# schematicEagle.net
KiCad netlist of a schematic drawn in EAGLE
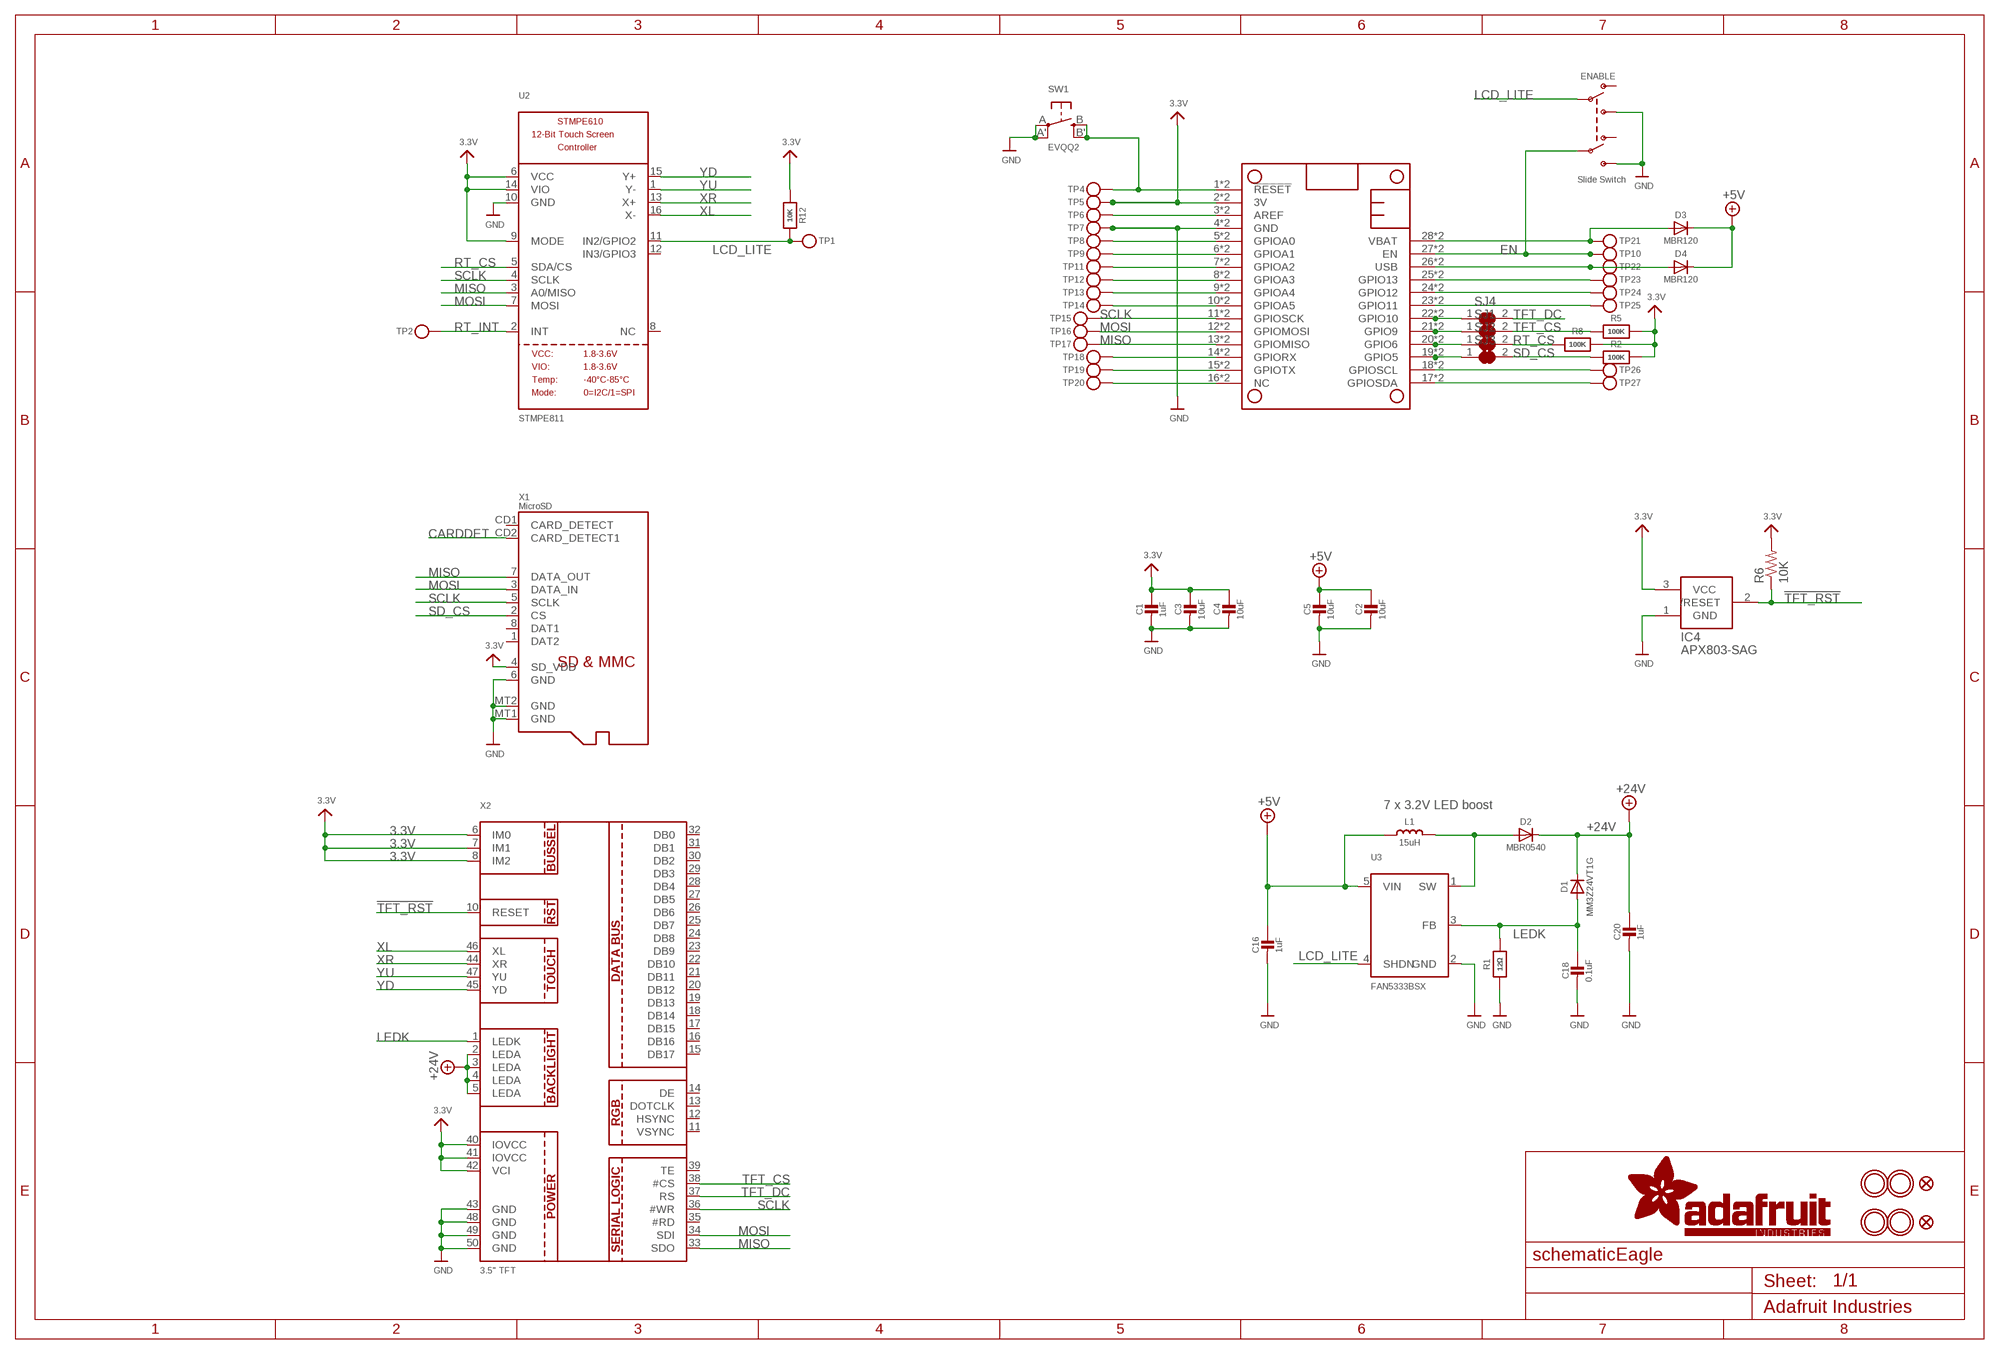
[diagram p0: schematic, sheet 1]

(export (version "E")
  (design (tool "Eeschema 10.0.6"))
  (components
    (comp (ref "C1")
      (value "1uF")
      (footprint "eagle-import:0805-NO")
      (libsource (lib "eagle-import") (part "CAP_CERAMIC0805-NOOUTLINE"))
    )
    (comp (ref "C2")
      (value "10uF")
      (footprint "eagle-import:0805-NO")
      (libsource (lib "eagle-import") (part "CAP_CERAMIC0805-NOOUTLINE"))
    )
    (comp (ref "C3")
      (value "10uF")
      (footprint "eagle-import:0805-NO")
      (libsource (lib "eagle-import") (part "CAP_CERAMIC0805-NOOUTLINE"))
    )
    (comp (ref "C4")
      (value "10uF")
      (footprint "eagle-import:0805-NO")
      (libsource (lib "eagle-import") (part "CAP_CERAMIC0805-NOOUTLINE"))
    )
    (comp (ref "C5")
      (value "10uF")
      (footprint "eagle-import:0805-NO")
      (libsource (lib "eagle-import") (part "CAP_CERAMIC0805-NOOUTLINE"))
    )
    (comp (ref "C16")
      (value "1uF")
      (footprint "eagle-import:0805-NO")
      (libsource (lib "eagle-import") (part "CAP_CERAMIC0805-NOOUTLINE"))
    )
    (comp (ref "C18")
      (value "0.1uF")
      (footprint "eagle-import:0805-NO")
      (libsource (lib "eagle-import") (part "CAP_CERAMIC0805-NOOUTLINE"))
    )
    (comp (ref "C20")
      (value "1uF")
      (footprint "eagle-import:0805-NO")
      (libsource (lib "eagle-import") (part "CAP_CERAMIC0805-NOOUTLINE"))
    )
    (comp (ref "D1")
      (value "MM3Z24VT1G")
      (footprint "eagle-import:SMADIODE")
      (libsource (lib "eagle-import") (part "DIODESMA"))
    )
    (comp (ref "D2")
      (value "MBR0540")
      (footprint "eagle-import:SOD-123")
      (libsource (lib "eagle-import") (part "DIODESOD-123"))
    )
    (comp (ref "D3")
      (value "MBR120")
      (footprint "eagle-import:SOD-123")
      (libsource (lib "eagle-import") (part "DIODESOD-123"))
    )
    (comp (ref "D4")
      (value "MBR120")
      (footprint "eagle-import:SOD-123")
      (libsource (lib "eagle-import") (part "DIODESOD-123"))
    )
    (comp (ref "ENABLE")
      (value "Slide Switch")
      (footprint "eagle-import:EG1390")
      (libsource (lib "eagle-import") (part "SWITCH_DPDTEG1390"))
    )
    (comp (ref "IC4")
      (value "APX803-SAG")
      (footprint "eagle-import:SOT23")
      (libsource (lib "eagle-import") (part "AXP083-SAG"))
    )
    (comp (ref "L1")
      (value "15uH")
      (footprint "eagle-import:INDUCTOR_5X5MM_NR5040_NOTHERMALS")
      (libsource (lib "eagle-import") (part "INDUCTORNR5040"))
    )
    (comp (ref "MS2")
      (value "FEATHERWING_SMTDUAL")
      (footprint "eagle-import:FEATHERWING_SMT2")
      (libsource (lib "eagle-import") (part "FEATHERWING_SMTDUAL"))
    )
    (comp (ref "R1")
      (value "12Ω")
      (footprint "eagle-import:0805-NO")
      (libsource (lib "eagle-import") (part "RESISTOR0805_NOOUTLINE"))
    )
    (comp (ref "R2")
      (value "100K")
      (footprint "eagle-import:0805-NO")
      (libsource (lib "eagle-import") (part "RESISTOR0805_NOOUTLINE"))
    )
    (comp (ref "R5")
      (value "100K")
      (footprint "eagle-import:0805-NO")
      (libsource (lib "eagle-import") (part "RESISTOR0805_NOOUTLINE"))
    )
    (comp (ref "R6")
      (value "10K")
      (footprint "eagle-import:R0805")
      (libsource (lib "eagle-import") (part "R-US_R0805"))
    )
    (comp (ref "R8")
      (value "100K")
      (footprint "eagle-import:0805-NO")
      (libsource (lib "eagle-import") (part "RESISTOR0805_NOOUTLINE"))
    )
    (comp (ref "R12")
      (value "10K")
      (footprint "eagle-import:0805-NO")
      (libsource (lib "eagle-import") (part "RESISTOR0805_NOOUTLINE"))
    )
    (comp (ref "SJ1")
      (value "SOLDERJUMPER_CLOSED")
      (footprint "eagle-import:SOLDERJUMPER_CLOSEDWIRE")
      (libsource (lib "eagle-import") (part "SOLDERJUMPER_CLOSED"))
    )
    (comp (ref "SJ2")
      (value "SOLDERJUMPER_CLOSED")
      (footprint "eagle-import:SOLDERJUMPER_CLOSEDWIRE")
      (libsource (lib "eagle-import") (part "SOLDERJUMPER_CLOSED"))
    )
    (comp (ref "SJ3")
      (value "SOLDERJUMPER_CLOSED")
      (footprint "eagle-import:SOLDERJUMPER_CLOSEDWIRE")
      (libsource (lib "eagle-import") (part "SOLDERJUMPER_CLOSED"))
    )
    (comp (ref "SJ4")
      (value "SOLDERJUMPER_CLOSED")
      (footprint "eagle-import:SOLDERJUMPER_CLOSEDWIRE")
      (libsource (lib "eagle-import") (part "SOLDERJUMPER_CLOSED"))
    )
    (comp (ref "SW1")
      (value "EVQQ2")
      (footprint "eagle-import:EVQ-Q2_SMALLER")
      (libsource (lib "eagle-import") (part "SWITCH_TACT_SMT_EVQQ2_SMALL"))
    )
    (comp (ref "TP1")
      (value "TESTPOINTPAD2MM")
      (footprint "eagle-import:TESTPOINT_PAD_2MM")
      (libsource (lib "eagle-import") (part "TESTPOINTPAD2MM"))
    )
    (comp (ref "TP2")
      (value "TESTPOINTPAD2MM")
      (footprint "eagle-import:TESTPOINT_PAD_2MM")
      (libsource (lib "eagle-import") (part "TESTPOINTPAD2MM"))
    )
    (comp (ref "TP4")
      (value "TESTPOINTPAD2MM")
      (footprint "eagle-import:TESTPOINT_PAD_2MM")
      (libsource (lib "eagle-import") (part "TESTPOINTPAD2MM"))
    )
    (comp (ref "TP5")
      (value "TESTPOINTPAD2MM")
      (footprint "eagle-import:TESTPOINT_PAD_2MM")
      (libsource (lib "eagle-import") (part "TESTPOINTPAD2MM"))
    )
    (comp (ref "TP6")
      (value "TESTPOINTPAD2MM")
      (footprint "eagle-import:TESTPOINT_PAD_2MM")
      (libsource (lib "eagle-import") (part "TESTPOINTPAD2MM"))
    )
    (comp (ref "TP7")
      (value "TESTPOINTPAD2MM")
      (footprint "eagle-import:TESTPOINT_PAD_2MM")
      (libsource (lib "eagle-import") (part "TESTPOINTPAD2MM"))
    )
    (comp (ref "TP8")
      (value "TESTPOINTPAD2MM")
      (footprint "eagle-import:TESTPOINT_PAD_2MM")
      (libsource (lib "eagle-import") (part "TESTPOINTPAD2MM"))
    )
    (comp (ref "TP9")
      (value "TESTPOINTPAD2MM")
      (footprint "eagle-import:TESTPOINT_PAD_2MM")
      (libsource (lib "eagle-import") (part "TESTPOINTPAD2MM"))
    )
    (comp (ref "TP10")
      (value "TESTPOINTPAD2MM")
      (footprint "eagle-import:TESTPOINT_PAD_2MM")
      (libsource (lib "eagle-import") (part "TESTPOINTPAD2MM"))
    )
    (comp (ref "TP11")
      (value "TESTPOINTPAD2MM")
      (footprint "eagle-import:TESTPOINT_PAD_2MM")
      (libsource (lib "eagle-import") (part "TESTPOINTPAD2MM"))
    )
    (comp (ref "TP12")
      (value "TESTPOINTPAD2MM")
      (footprint "eagle-import:TESTPOINT_PAD_2MM")
      (libsource (lib "eagle-import") (part "TESTPOINTPAD2MM"))
    )
    (comp (ref "TP13")
      (value "TESTPOINTPAD2MM")
      (footprint "eagle-import:TESTPOINT_PAD_2MM")
      (libsource (lib "eagle-import") (part "TESTPOINTPAD2MM"))
    )
    (comp (ref "TP14")
      (value "TESTPOINTPAD2MM")
      (footprint "eagle-import:TESTPOINT_PAD_2MM")
      (libsource (lib "eagle-import") (part "TESTPOINTPAD2MM"))
    )
    (comp (ref "TP15")
      (value "TESTPOINTPAD2MM")
      (footprint "eagle-import:TESTPOINT_PAD_2MM")
      (libsource (lib "eagle-import") (part "TESTPOINTPAD2MM"))
    )
    (comp (ref "TP16")
      (value "TESTPOINTPAD2MM")
      (footprint "eagle-import:TESTPOINT_PAD_2MM")
      (libsource (lib "eagle-import") (part "TESTPOINTPAD2MM"))
    )
    (comp (ref "TP17")
      (value "TESTPOINTPAD2MM")
      (footprint "eagle-import:TESTPOINT_PAD_2MM")
      (libsource (lib "eagle-import") (part "TESTPOINTPAD2MM"))
    )
    (comp (ref "TP18")
      (value "TESTPOINTPAD2MM")
      (footprint "eagle-import:TESTPOINT_PAD_2MM")
      (libsource (lib "eagle-import") (part "TESTPOINTPAD2MM"))
    )
    (comp (ref "TP19")
      (value "TESTPOINTPAD2MM")
      (footprint "eagle-import:TESTPOINT_PAD_2MM")
      (libsource (lib "eagle-import") (part "TESTPOINTPAD2MM"))
    )
    (comp (ref "TP20")
      (value "TESTPOINTPAD2MM")
      (footprint "eagle-import:TESTPOINT_PAD_2MM")
      (libsource (lib "eagle-import") (part "TESTPOINTPAD2MM"))
    )
    (comp (ref "TP21")
      (value "TESTPOINTPAD2MM")
      (footprint "eagle-import:TESTPOINT_PAD_2MM")
      (libsource (lib "eagle-import") (part "TESTPOINTPAD2MM"))
    )
    (comp (ref "TP22")
      (value "TESTPOINTPAD2MM")
      (footprint "eagle-import:TESTPOINT_PAD_2MM")
      (libsource (lib "eagle-import") (part "TESTPOINTPAD2MM"))
    )
    (comp (ref "TP23")
      (value "TESTPOINTPAD2MM")
      (footprint "eagle-import:TESTPOINT_PAD_2MM")
      (libsource (lib "eagle-import") (part "TESTPOINTPAD2MM"))
    )
    (comp (ref "TP24")
      (value "TESTPOINTPAD2MM")
      (footprint "eagle-import:TESTPOINT_PAD_2MM")
      (libsource (lib "eagle-import") (part "TESTPOINTPAD2MM"))
    )
    (comp (ref "TP25")
      (value "TESTPOINTPAD2MM")
      (footprint "eagle-import:TESTPOINT_PAD_2MM")
      (libsource (lib "eagle-import") (part "TESTPOINTPAD2MM"))
    )
    (comp (ref "TP26")
      (value "TESTPOINTPAD2MM")
      (footprint "eagle-import:TESTPOINT_PAD_2MM")
      (libsource (lib "eagle-import") (part "TESTPOINTPAD2MM"))
    )
    (comp (ref "TP27")
      (value "TESTPOINTPAD2MM")
      (footprint "eagle-import:TESTPOINT_PAD_2MM")
      (libsource (lib "eagle-import") (part "TESTPOINTPAD2MM"))
    )
    (comp (ref "U$7")
      (value "MOUNTINGHOLE3.0THIN")
      (footprint "eagle-import:MOUNTINGHOLE_3.0_PLATEDTHIN")
      (libsource (lib "eagle-import") (part "MOUNTINGHOLE3.0THIN"))
    )
    (comp (ref "U$9")
      (value "FIDUCIAL_1MM")
      (footprint "eagle-import:FIDUCIAL_1MM")
      (libsource (lib "eagle-import") (part "FIDUCIAL_1MM"))
    )
    (comp (ref "U$15")
      (value "MOUNTINGHOLE3.0THIN")
      (footprint "eagle-import:MOUNTINGHOLE_3.0_PLATEDTHIN")
      (libsource (lib "eagle-import") (part "MOUNTINGHOLE3.0THIN"))
    )
    (comp (ref "U$16")
      (value "MOUNTINGHOLE3.0THIN")
      (footprint "eagle-import:MOUNTINGHOLE_3.0_PLATEDTHIN")
      (libsource (lib "eagle-import") (part "MOUNTINGHOLE3.0THIN"))
    )
    (comp (ref "U$17")
      (value "MOUNTINGHOLE3.0THIN")
      (footprint "eagle-import:MOUNTINGHOLE_3.0_PLATEDTHIN")
      (libsource (lib "eagle-import") (part "MOUNTINGHOLE3.0THIN"))
    )
    (comp (ref "U$23")
      (value "FIDUCIAL_1MM")
      (footprint "eagle-import:FIDUCIAL_1MM")
      (libsource (lib "eagle-import") (part "FIDUCIAL_1MM"))
    )
    (comp (ref "U2")
      (value "STMPE811")
      (footprint "eagle-import:QFN16_3MM")
      (libsource (lib "eagle-import") (part "STMPE610"))
    )
    (comp (ref "U3")
      (value "FAN5333BSX")
      (footprint "eagle-import:SOT23-5@1")
      (libsource (lib "eagle-import") (part "FAN5331"))
    )
    (comp (ref "X1")
      (value "MicroSD")
      (footprint "eagle-import:MICROSD")
      (libsource (lib "eagle-import") (part "MICROSD"))
    )
    (comp (ref "X2")
      (value "3.5\" TFT")
      (footprint "eagle-import:TFT_3.5IN_320X480_50PIN")
      (libsource (lib "eagle-import") (part "DISP_LCD_3.5IN_320X480_50PIN"))
    )
  )
  (nets
    (net (code "1") (name "+5V") (class "Default")
      (node (ref "C16") (pin "1") (pinfunction "1_1") (pintype "passive"))
      (node (ref "C2") (pin "1") (pinfunction "1_1") (pintype "passive"))
      (node (ref "C5") (pin "1") (pinfunction "1_1") (pintype "passive"))
      (node (ref "D3") (pin "C") (pinfunction "C_C") (pintype "passive"))
      (node (ref "D4") (pin "C") (pinfunction "C_C") (pintype "passive"))
      (node (ref "L1") (pin "P$1") (pinfunction "1_P$1") (pintype "passive"))
      (node (ref "U3") (pin "5") (pinfunction "VIN_5") (pintype "bidirectional"))
    )
    (net (code "2") (name "+24V") (class "Default")
      (node (ref "C20") (pin "1") (pinfunction "1_1") (pintype "passive"))
      (node (ref "D1") (pin "C") (pinfunction "C_C") (pintype "passive"))
      (node (ref "D2") (pin "C") (pinfunction "C_C") (pintype "passive"))
      (node (ref "X2") (pin "2") (pinfunction "LEDA_2") (pintype "bidirectional"))
      (node (ref "X2") (pin "3") (pinfunction "LEDA_3") (pintype "bidirectional"))
      (node (ref "X2") (pin "4") (pinfunction "LEDA_4") (pintype "bidirectional"))
      (node (ref "X2") (pin "5") (pinfunction "LEDA_5") (pintype "bidirectional"))
    )
    (net (code "3") (name "/CARDDET") (class "Default")
      (node (ref "X1") (pin "CD2") (pinfunction "CARD_DETECT1_CD2") (pintype "passive"))
    )
    (net (code "4") (name "/EN") (class "Default")
      (node (ref "ENABLE") (pin "P2") (pinfunction "P2_P2") (pintype "passive"))
      (node (ref "MS2") (pin "27") (pinfunction "EN_27") (pintype "passive"))
      (node (ref "MS2") (pin "27'") (pinfunction "EN_27'") (pintype "passive"))
      (node (ref "TP10") (pin "P$1") (pinfunction "P$1_P$1") (pintype "bidirectional"))
    )
    (net (code "5") (name "/LCD_LITE") (class "Default")
      (node (ref "ENABLE") (pin "P1") (pinfunction "P1_P1") (pintype "passive"))
      (node (ref "R12") (pin "2") (pinfunction "2_2") (pintype "passive"))
      (node (ref "TP1") (pin "P$1") (pinfunction "P$1_P$1") (pintype "bidirectional"))
      (node (ref "U2") (pin "11") (pinfunction "IN2/GPIO2_11") (pintype "bidirectional"))
      (node (ref "U3") (pin "4") (pinfunction "SHDN_4") (pintype "bidirectional"))
    )
    (net (code "6") (name "/LEDK") (class "Default")
      (node (ref "C18") (pin "1") (pinfunction "1_1") (pintype "passive"))
      (node (ref "D1") (pin "A") (pinfunction "A_A") (pintype "passive"))
      (node (ref "R1") (pin "2") (pinfunction "2_2") (pintype "passive"))
      (node (ref "U3") (pin "3") (pinfunction "FB_3") (pintype "bidirectional"))
      (node (ref "X2") (pin "1") (pinfunction "LEDK_1") (pintype "bidirectional"))
    )
    (net (code "7") (name "/MISO") (class "Default")
      (node (ref "MS2") (pin "13") (pinfunction "GPIOMISO_13") (pintype "bidirectional"))
      (node (ref "MS2") (pin "13'") (pinfunction "GPIOMISO_13'") (pintype "bidirectional"))
      (node (ref "TP17") (pin "P$1") (pinfunction "P$1_P$1") (pintype "bidirectional"))
      (node (ref "U2") (pin "3") (pinfunction "A0/MISO_3") (pintype "bidirectional"))
      (node (ref "X1") (pin "7") (pinfunction "DATA_OUT_7") (pintype "output"))
      (node (ref "X2") (pin "33") (pinfunction "SDO_33") (pintype "bidirectional"))
    )
    (net (code "8") (name "/MOSI") (class "Default")
      (node (ref "MS2") (pin "12") (pinfunction "GPIOMOSI_12") (pintype "bidirectional"))
      (node (ref "MS2") (pin "12'") (pinfunction "GPIOMOSI_12'") (pintype "bidirectional"))
      (node (ref "TP16") (pin "P$1") (pinfunction "P$1_P$1") (pintype "bidirectional"))
      (node (ref "U2") (pin "7") (pinfunction "MOSI_7") (pintype "input"))
      (node (ref "X1") (pin "3") (pinfunction "DATA_IN_3") (pintype "input"))
      (node (ref "X2") (pin "34") (pinfunction "SDI_34") (pintype "bidirectional"))
    )
    (net (code "9") (name "/RT_CS") (class "Default")
      (node (ref "R8") (pin "1") (pinfunction "1_1") (pintype "passive"))
      (node (ref "SJ2") (pin "2") (pinfunction "2_2") (pintype "passive"))
      (node (ref "U2") (pin "5") (pinfunction "SDA/CS_5") (pintype "bidirectional"))
    )
    (net (code "10") (name "/RT_INT") (class "Default")
      (node (ref "TP2") (pin "P$1") (pinfunction "P$1_P$1") (pintype "bidirectional"))
      (node (ref "U2") (pin "2") (pinfunction "INT_2") (pintype "output"))
    )
    (net (code "11") (name "/SCLK") (class "Default")
      (node (ref "MS2") (pin "11") (pinfunction "GPIOSCK_11") (pintype "bidirectional"))
      (node (ref "MS2") (pin "11'") (pinfunction "GPIOSCK_11'") (pintype "bidirectional"))
      (node (ref "TP15") (pin "P$1") (pinfunction "P$1_P$1") (pintype "bidirectional"))
      (node (ref "U2") (pin "4") (pinfunction "SCLK_4") (pintype "bidirectional"))
      (node (ref "X1") (pin "5") (pinfunction "SCLK_5") (pintype "input"))
      (node (ref "X2") (pin "36") (pinfunction "#WR_36") (pintype "bidirectional"))
    )
    (net (code "12") (name "/SD_CS") (class "Default")
      (node (ref "R2") (pin "1") (pinfunction "1_1") (pintype "passive"))
      (node (ref "SJ3") (pin "2") (pinfunction "2_2") (pintype "passive"))
      (node (ref "X1") (pin "2") (pinfunction "CS_2") (pintype "input"))
    )
    (net (code "13") (name "/TFT_CS") (class "Default")
      (node (ref "R5") (pin "1") (pinfunction "1_1") (pintype "passive"))
      (node (ref "SJ1") (pin "2") (pinfunction "2_2") (pintype "passive"))
      (node (ref "X2") (pin "38") (pinfunction "#CS_38") (pintype "bidirectional"))
    )
    (net (code "14") (name "/TFT_DC") (class "Default")
      (node (ref "SJ4") (pin "2") (pinfunction "2_2") (pintype "passive"))
      (node (ref "X2") (pin "37") (pinfunction "RS_37") (pintype "bidirectional"))
    )
    (net (code "15") (name "/XL") (class "Default")
      (node (ref "U2") (pin "16") (pinfunction "X-_16") (pintype "input"))
      (node (ref "X2") (pin "46") (pinfunction "XL_46") (pintype "bidirectional"))
    )
    (net (code "16") (name "/XR") (class "Default")
      (node (ref "U2") (pin "13") (pinfunction "X+_13") (pintype "input"))
      (node (ref "X2") (pin "44") (pinfunction "XR_44") (pintype "bidirectional"))
    )
    (net (code "17") (name "/YD") (class "Default")
      (node (ref "U2") (pin "15") (pinfunction "Y+_15") (pintype "input"))
      (node (ref "X2") (pin "45") (pinfunction "YD_45") (pintype "bidirectional"))
    )
    (net (code "18") (name "/YU") (class "Default")
      (node (ref "U2") (pin "1") (pinfunction "Y-_1") (pintype "input"))
      (node (ref "X2") (pin "47") (pinfunction "YU_47") (pintype "bidirectional"))
    )
    (net (code "19") (name "/~{TFT_RST}") (class "Default")
      (node (ref "IC4") (pin "2") (pinfunction "/RESET_2") (pintype "output"))
      (node (ref "R6") (pin "1") (pinfunction "1_1") (pintype "passive"))
      (node (ref "X2") (pin "10") (pinfunction "RESET_10") (pintype "bidirectional"))
    )
    (net (code "20") (name "3.3V") (class "Default")
      (node (ref "C1") (pin "1") (pinfunction "1_1") (pintype "passive"))
      (node (ref "C3") (pin "1") (pinfunction "1_1") (pintype "passive"))
      (node (ref "C4") (pin "1") (pinfunction "1_1") (pintype "passive"))
      (node (ref "IC4") (pin "3") (pinfunction "VCC_3") (pintype "power_in"))
      (node (ref "MS2") (pin "2") (pinfunction "3V_2") (pintype "power_in"))
      (node (ref "MS2") (pin "2'") (pinfunction "3V_2'") (pintype "power_in"))
      (node (ref "R12") (pin "1") (pinfunction "1_1") (pintype "passive"))
      (node (ref "R2") (pin "2") (pinfunction "2_2") (pintype "passive"))
      (node (ref "R5") (pin "2") (pinfunction "2_2") (pintype "passive"))
      (node (ref "R6") (pin "2") (pinfunction "2_2") (pintype "passive"))
      (node (ref "R8") (pin "2") (pinfunction "2_2") (pintype "passive"))
      (node (ref "TP5") (pin "P$1") (pinfunction "P$1_P$1") (pintype "bidirectional"))
      (node (ref "U2") (pin "14") (pinfunction "VIO_14") (pintype "power_in"))
      (node (ref "U2") (pin "6") (pinfunction "VCC_6") (pintype "power_in"))
      (node (ref "U2") (pin "9") (pinfunction "MODE_9") (pintype "input"))
      (node (ref "X1") (pin "4") (pinfunction "SD_VDD_4") (pintype "power_in"))
      (node (ref "X2") (pin "40") (pinfunction "IOVCC_40") (pintype "bidirectional"))
      (node (ref "X2") (pin "41") (pinfunction "IOVCC_41") (pintype "bidirectional"))
      (node (ref "X2") (pin "42") (pinfunction "VCI_42") (pintype "bidirectional"))
      (node (ref "X2") (pin "6") (pinfunction "IM0_6") (pintype "bidirectional"))
      (node (ref "X2") (pin "7") (pinfunction "IM1_7") (pintype "bidirectional"))
      (node (ref "X2") (pin "8") (pinfunction "IM2_8") (pintype "bidirectional"))
    )
    (net (code "21") (name "GND") (class "Default")
      (node (ref "C1") (pin "2") (pinfunction "2_2") (pintype "passive"))
      (node (ref "C16") (pin "2") (pinfunction "2_2") (pintype "passive"))
      (node (ref "C18") (pin "2") (pinfunction "2_2") (pintype "passive"))
      (node (ref "C2") (pin "2") (pinfunction "2_2") (pintype "passive"))
      (node (ref "C20") (pin "2") (pinfunction "2_2") (pintype "passive"))
      (node (ref "C3") (pin "2") (pinfunction "2_2") (pintype "passive"))
      (node (ref "C4") (pin "2") (pinfunction "2_2") (pintype "passive"))
      (node (ref "C5") (pin "2") (pinfunction "2_2") (pintype "passive"))
      (node (ref "ENABLE") (pin "S1") (pinfunction "S1_S1") (pintype "passive"))
      (node (ref "ENABLE") (pin "S2") (pinfunction "S2_S2") (pintype "passive"))
      (node (ref "IC4") (pin "1") (pinfunction "GND_1") (pintype "power_in"))
      (node (ref "MS2") (pin "4") (pinfunction "GND_4") (pintype "power_in"))
      (node (ref "MS2") (pin "4'") (pinfunction "GND_4'") (pintype "power_in"))
      (node (ref "R1") (pin "1") (pinfunction "1_1") (pintype "passive"))
      (node (ref "SW1") (pin "A") (pinfunction "P_A") (pintype "passive"))
      (node (ref "SW1") (pin "A'") (pinfunction "P1_A'") (pintype "passive"))
      (node (ref "TP7") (pin "P$1") (pinfunction "P$1_P$1") (pintype "bidirectional"))
      (node (ref "U2") (pin "10") (pinfunction "GND_10") (pintype "power_in"))
      (node (ref "U3") (pin "2") (pinfunction "GND_2") (pintype "bidirectional"))
      (node (ref "X1") (pin "6") (pinfunction "GND_6") (pintype "power_in"))
      (node (ref "X1") (pin "MT1") (pinfunction "GND_MT1") (pintype "power_in"))
      (node (ref "X1") (pin "MT2") (pinfunction "GND_MT2") (pintype "power_in"))
      (node (ref "X2") (pin "43") (pinfunction "GND_43") (pintype "bidirectional"))
      (node (ref "X2") (pin "48") (pinfunction "GND_48") (pintype "bidirectional"))
      (node (ref "X2") (pin "49") (pinfunction "GND_49") (pintype "bidirectional"))
      (node (ref "X2") (pin "50") (pinfunction "GND_50") (pintype "bidirectional"))
    )
    (net (code "22") (name "Net-(D3-PadA)") (class "Default")
      (node (ref "D3") (pin "A") (pinfunction "A_A") (pintype "passive"))
      (node (ref "MS2") (pin "28") (pinfunction "VBAT_28") (pintype "power_in"))
      (node (ref "MS2") (pin "28'") (pinfunction "VBAT_28'") (pintype "power_in"))
      (node (ref "TP21") (pin "P$1") (pinfunction "P$1_P$1") (pintype "bidirectional"))
    )
    (net (code "23") (name "Net-(D4-PadA)") (class "Default")
      (node (ref "D4") (pin "A") (pinfunction "A_A") (pintype "passive"))
      (node (ref "MS2") (pin "26") (pinfunction "USB_26") (pintype "power_in"))
      (node (ref "MS2") (pin "26'") (pinfunction "USB_26'") (pintype "power_in"))
      (node (ref "TP22") (pin "P$1") (pinfunction "P$1_P$1") (pintype "bidirectional"))
    )
    (net (code "24") (name "Net-(L1-2)") (class "Default")
      (node (ref "D2") (pin "A") (pinfunction "A_A") (pintype "passive"))
      (node (ref "L1") (pin "P$2") (pinfunction "2_P$2") (pintype "passive"))
      (node (ref "U3") (pin "1") (pinfunction "SW_1") (pintype "bidirectional"))
    )
    (net (code "25") (name "Net-(MS2-AREF-Pad3')") (class "Default")
      (node (ref "MS2") (pin "3") (pinfunction "AREF_3") (pintype "passive"))
      (node (ref "MS2") (pin "3'") (pinfunction "AREF_3'") (pintype "passive"))
      (node (ref "TP6") (pin "P$1") (pinfunction "P$1_P$1") (pintype "bidirectional"))
    )
    (net (code "26") (name "Net-(MS2-GPIO5-Pad19')") (class "Default")
      (node (ref "MS2") (pin "19") (pinfunction "GPIO5_19") (pintype "bidirectional"))
      (node (ref "MS2") (pin "19'") (pinfunction "GPIO5_19'") (pintype "bidirectional"))
      (node (ref "SJ3") (pin "1") (pinfunction "1_1") (pintype "passive"))
    )
    (net (code "27") (name "Net-(MS2-GPIO6-Pad20')") (class "Default")
      (node (ref "MS2") (pin "20") (pinfunction "GPIO6_20") (pintype "bidirectional"))
      (node (ref "MS2") (pin "20'") (pinfunction "GPIO6_20'") (pintype "bidirectional"))
      (node (ref "SJ2") (pin "1") (pinfunction "1_1") (pintype "passive"))
    )
    (net (code "28") (name "Net-(MS2-GPIO9-Pad21')") (class "Default")
      (node (ref "MS2") (pin "21") (pinfunction "GPIO9_21") (pintype "bidirectional"))
      (node (ref "MS2") (pin "21'") (pinfunction "GPIO9_21'") (pintype "bidirectional"))
      (node (ref "SJ1") (pin "1") (pinfunction "1_1") (pintype "passive"))
    )
    (net (code "29") (name "Net-(MS2-GPIO10-Pad22')") (class "Default")
      (node (ref "MS2") (pin "22") (pinfunction "GPIO10_22") (pintype "bidirectional"))
      (node (ref "MS2") (pin "22'") (pinfunction "GPIO10_22'") (pintype "bidirectional"))
      (node (ref "SJ4") (pin "1") (pinfunction "1_1") (pintype "passive"))
    )
    (net (code "30") (name "Net-(MS2-GPIO11-Pad23')") (class "Default")
      (node (ref "MS2") (pin "23") (pinfunction "GPIO11_23") (pintype "bidirectional"))
      (node (ref "MS2") (pin "23'") (pinfunction "GPIO11_23'") (pintype "bidirectional"))
      (node (ref "TP25") (pin "P$1") (pinfunction "P$1_P$1") (pintype "bidirectional"))
    )
    (net (code "31") (name "Net-(MS2-GPIO12-Pad24')") (class "Default")
      (node (ref "MS2") (pin "24") (pinfunction "GPIO12_24") (pintype "bidirectional"))
      (node (ref "MS2") (pin "24'") (pinfunction "GPIO12_24'") (pintype "bidirectional"))
      (node (ref "TP24") (pin "P$1") (pinfunction "P$1_P$1") (pintype "bidirectional"))
    )
    (net (code "32") (name "Net-(MS2-GPIO13-Pad25')") (class "Default")
      (node (ref "MS2") (pin "25") (pinfunction "GPIO13_25") (pintype "bidirectional"))
      (node (ref "MS2") (pin "25'") (pinfunction "GPIO13_25'") (pintype "bidirectional"))
      (node (ref "TP23") (pin "P$1") (pinfunction "P$1_P$1") (pintype "bidirectional"))
    )
    (net (code "33") (name "Net-(MS2-GPIOA0-Pad5')") (class "Default")
      (node (ref "MS2") (pin "5") (pinfunction "GPIOA0_5") (pintype "bidirectional"))
      (node (ref "MS2") (pin "5'") (pinfunction "GPIOA0_5'") (pintype "bidirectional"))
      (node (ref "TP8") (pin "P$1") (pinfunction "P$1_P$1") (pintype "bidirectional"))
    )
    (net (code "34") (name "Net-(MS2-GPIOA1-Pad6')") (class "Default")
      (node (ref "MS2") (pin "6") (pinfunction "GPIOA1_6") (pintype "bidirectional"))
      (node (ref "MS2") (pin "6'") (pinfunction "GPIOA1_6'") (pintype "bidirectional"))
      (node (ref "TP9") (pin "P$1") (pinfunction "P$1_P$1") (pintype "bidirectional"))
    )
    (net (code "35") (name "Net-(MS2-GPIOA2-Pad7')") (class "Default")
      (node (ref "MS2") (pin "7") (pinfunction "GPIOA2_7") (pintype "bidirectional"))
      (node (ref "MS2") (pin "7'") (pinfunction "GPIOA2_7'") (pintype "bidirectional"))
      (node (ref "TP11") (pin "P$1") (pinfunction "P$1_P$1") (pintype "bidirectional"))
    )
    (net (code "36") (name "Net-(MS2-GPIOA3-Pad8')") (class "Default")
      (node (ref "MS2") (pin "8") (pinfunction "GPIOA3_8") (pintype "bidirectional"))
      (node (ref "MS2") (pin "8'") (pinfunction "GPIOA3_8'") (pintype "bidirectional"))
      (node (ref "TP12") (pin "P$1") (pinfunction "P$1_P$1") (pintype "bidirectional"))
    )
    (net (code "37") (name "Net-(MS2-GPIOA4-Pad9')") (class "Default")
      (node (ref "MS2") (pin "9") (pinfunction "GPIOA4_9") (pintype "bidirectional"))
      (node (ref "MS2") (pin "9'") (pinfunction "GPIOA4_9'") (pintype "bidirectional"))
      (node (ref "TP13") (pin "P$1") (pinfunction "P$1_P$1") (pintype "bidirectional"))
    )
    (net (code "38") (name "Net-(MS2-GPIOA5-Pad10')") (class "Default")
      (node (ref "MS2") (pin "10") (pinfunction "GPIOA5_10") (pintype "bidirectional"))
      (node (ref "MS2") (pin "10'") (pinfunction "GPIOA5_10'") (pintype "bidirectional"))
      (node (ref "TP14") (pin "P$1") (pinfunction "P$1_P$1") (pintype "bidirectional"))
    )
    (net (code "39") (name "Net-(MS2-GPIORX-Pad14')") (class "Default")
      (node (ref "MS2") (pin "14") (pinfunction "GPIORX_14") (pintype "bidirectional"))
      (node (ref "MS2") (pin "14'") (pinfunction "GPIORX_14'") (pintype "bidirectional"))
      (node (ref "TP18") (pin "P$1") (pinfunction "P$1_P$1") (pintype "bidirectional"))
    )
    (net (code "40") (name "Net-(MS2-GPIOSCL-Pad18')") (class "Default")
      (node (ref "MS2") (pin "18") (pinfunction "GPIOSCL_18") (pintype "bidirectional"))
      (node (ref "MS2") (pin "18'") (pinfunction "GPIOSCL_18'") (pintype "bidirectional"))
      (node (ref "TP26") (pin "P$1") (pinfunction "P$1_P$1") (pintype "bidirectional"))
    )
    (net (code "41") (name "Net-(MS2-GPIOSDA-Pad17')") (class "Default")
      (node (ref "MS2") (pin "17") (pinfunction "GPIOSDA_17") (pintype "bidirectional"))
      (node (ref "MS2") (pin "17'") (pinfunction "GPIOSDA_17'") (pintype "bidirectional"))
      (node (ref "TP27") (pin "P$1") (pinfunction "P$1_P$1") (pintype "bidirectional"))
    )
    (net (code "42") (name "Net-(MS2-GPIOTX-Pad15')") (class "Default")
      (node (ref "MS2") (pin "15") (pinfunction "GPIOTX_15") (pintype "bidirectional"))
      (node (ref "MS2") (pin "15'") (pinfunction "GPIOTX_15'") (pintype "bidirectional"))
      (node (ref "TP19") (pin "P$1") (pinfunction "P$1_P$1") (pintype "bidirectional"))
    )
    (net (code "43") (name "Net-(MS2-NC-Pad16')") (class "Default")
      (node (ref "MS2") (pin "16") (pinfunction "NC_16") (pintype "passive"))
      (node (ref "MS2") (pin "16'") (pinfunction "NC_16'") (pintype "passive"))
      (node (ref "TP20") (pin "P$1") (pinfunction "P$1_P$1") (pintype "bidirectional"))
    )
    (net (code "44") (name "Net-(SW1-S)") (class "Default")
      (node (ref "MS2") (pin "1") (pinfunction "~{RESET}_1") (pintype "input"))
      (node (ref "MS2") (pin "1'") (pinfunction "~{RESET}_1'") (pintype "input"))
      (node (ref "SW1") (pin "B") (pinfunction "S_B") (pintype "passive"))
      (node (ref "SW1") (pin "B'") (pinfunction "S1_B'") (pintype "passive"))
      (node (ref "TP4") (pin "P$1") (pinfunction "P$1_P$1") (pintype "bidirectional"))
    )
    (net (code "45") (name "unconnected-(ENABLE-PadO1)") (class "Default")
      (node (ref "ENABLE") (pin "O1") (pinfunction "O1_O1") (pintype "passive"))
    )
    (net (code "46") (name "unconnected-(ENABLE-PadO2)") (class "Default")
      (node (ref "ENABLE") (pin "O2") (pinfunction "O2_O2") (pintype "passive"))
    )
    (net (code "47") (name "unconnected-(U2-IN3{slash}GPIO3-Pad12)") (class "Default")
      (node (ref "U2") (pin "12") (pinfunction "IN3/GPIO3_12") (pintype "bidirectional"))
    )
    (net (code "48") (name "unconnected-(U2-NC-Pad8)") (class "Default")
      (node (ref "U2") (pin "8") (pinfunction "NC_8") (pintype "no_connect"))
    )
    (net (code "49") (name "unconnected-(X1-CARD_DETECT-PadCD1)") (class "Default")
      (node (ref "X1") (pin "CD1") (pinfunction "CARD_DETECT_CD1") (pintype "passive"))
    )
    (net (code "50") (name "unconnected-(X1-DAT1-Pad8)") (class "Default")
      (node (ref "X1") (pin "8") (pinfunction "DAT1_8") (pintype "bidirectional"))
    )
    (net (code "51") (name "unconnected-(X1-DAT2-Pad1)") (class "Default")
      (node (ref "X1") (pin "1") (pinfunction "DAT2_1") (pintype "bidirectional"))
    )
    (net (code "52") (name "unconnected-(X2-#RD-Pad35)") (class "Default")
      (node (ref "X2") (pin "35") (pinfunction "#RD_35") (pintype "bidirectional"))
    )
    (net (code "53") (name "unconnected-(X2-DB0-Pad32)") (class "Default")
      (node (ref "X2") (pin "32") (pinfunction "DB0_32") (pintype "bidirectional"))
    )
    (net (code "54") (name "unconnected-(X2-DB1-Pad31)") (class "Default")
      (node (ref "X2") (pin "31") (pinfunction "DB1_31") (pintype "bidirectional"))
    )
    (net (code "55") (name "unconnected-(X2-DB2-Pad30)") (class "Default")
      (node (ref "X2") (pin "30") (pinfunction "DB2_30") (pintype "bidirectional"))
    )
    (net (code "56") (name "unconnected-(X2-DB3-Pad29)") (class "Default")
      (node (ref "X2") (pin "29") (pinfunction "DB3_29") (pintype "bidirectional"))
    )
    (net (code "57") (name "unconnected-(X2-DB4-Pad28)") (class "Default")
      (node (ref "X2") (pin "28") (pinfunction "DB4_28") (pintype "bidirectional"))
    )
    (net (code "58") (name "unconnected-(X2-DB5-Pad27)") (class "Default")
      (node (ref "X2") (pin "27") (pinfunction "DB5_27") (pintype "bidirectional"))
    )
    (net (code "59") (name "unconnected-(X2-DB6-Pad26)") (class "Default")
      (node (ref "X2") (pin "26") (pinfunction "DB6_26") (pintype "bidirectional"))
    )
    (net (code "60") (name "unconnected-(X2-DB7-Pad25)") (class "Default")
      (node (ref "X2") (pin "25") (pinfunction "DB7_25") (pintype "bidirectional"))
    )
    (net (code "61") (name "unconnected-(X2-DB8-Pad24)") (class "Default")
      (node (ref "X2") (pin "24") (pinfunction "DB8_24") (pintype "bidirectional"))
    )
    (net (code "62") (name "unconnected-(X2-DB9-Pad23)") (class "Default")
      (node (ref "X2") (pin "23") (pinfunction "DB9_23") (pintype "bidirectional"))
    )
    (net (code "63") (name "unconnected-(X2-DB10-Pad22)") (class "Default")
      (node (ref "X2") (pin "22") (pinfunction "DB10_22") (pintype "bidirectional"))
    )
    (net (code "64") (name "unconnected-(X2-DB11-Pad21)") (class "Default")
      (node (ref "X2") (pin "21") (pinfunction "DB11_21") (pintype "bidirectional"))
    )
    (net (code "65") (name "unconnected-(X2-DB12-Pad20)") (class "Default")
      (node (ref "X2") (pin "20") (pinfunction "DB12_20") (pintype "bidirectional"))
    )
    (net (code "66") (name "unconnected-(X2-DB13-Pad19)") (class "Default")
      (node (ref "X2") (pin "19") (pinfunction "DB13_19") (pintype "bidirectional"))
    )
    (net (code "67") (name "unconnected-(X2-DB14-Pad18)") (class "Default")
      (node (ref "X2") (pin "18") (pinfunction "DB14_18") (pintype "bidirectional"))
    )
    (net (code "68") (name "unconnected-(X2-DB15-Pad17)") (class "Default")
      (node (ref "X2") (pin "17") (pinfunction "DB15_17") (pintype "bidirectional"))
    )
    (net (code "69") (name "unconnected-(X2-DB16-Pad16)") (class "Default")
      (node (ref "X2") (pin "16") (pinfunction "DB16_16") (pintype "bidirectional"))
    )
    (net (code "70") (name "unconnected-(X2-DB17-Pad15)") (class "Default")
      (node (ref "X2") (pin "15") (pinfunction "DB17_15") (pintype "bidirectional"))
    )
    (net (code "71") (name "unconnected-(X2-DE-Pad14)") (class "Default")
      (node (ref "X2") (pin "14") (pinfunction "DE_14") (pintype "bidirectional"))
    )
    (net (code "72") (name "unconnected-(X2-DOTCLK-Pad13)") (class "Default")
      (node (ref "X2") (pin "13") (pinfunction "DOTCLK_13") (pintype "bidirectional"))
    )
    (net (code "73") (name "unconnected-(X2-HSYNC-Pad12)") (class "Default")
      (node (ref "X2") (pin "12") (pinfunction "HSYNC_12") (pintype "bidirectional"))
    )
    (net (code "74") (name "unconnected-(X2-TE-Pad39)") (class "Default")
      (node (ref "X2") (pin "39") (pinfunction "TE_39") (pintype "bidirectional"))
    )
    (net (code "75") (name "unconnected-(X2-VSYNC-Pad11)") (class "Default")
      (node (ref "X2") (pin "11") (pinfunction "VSYNC_11") (pintype "bidirectional"))
    )
  )
)
